# FAN.net
KiCad netlist of a schematic drawn in Altium Designer
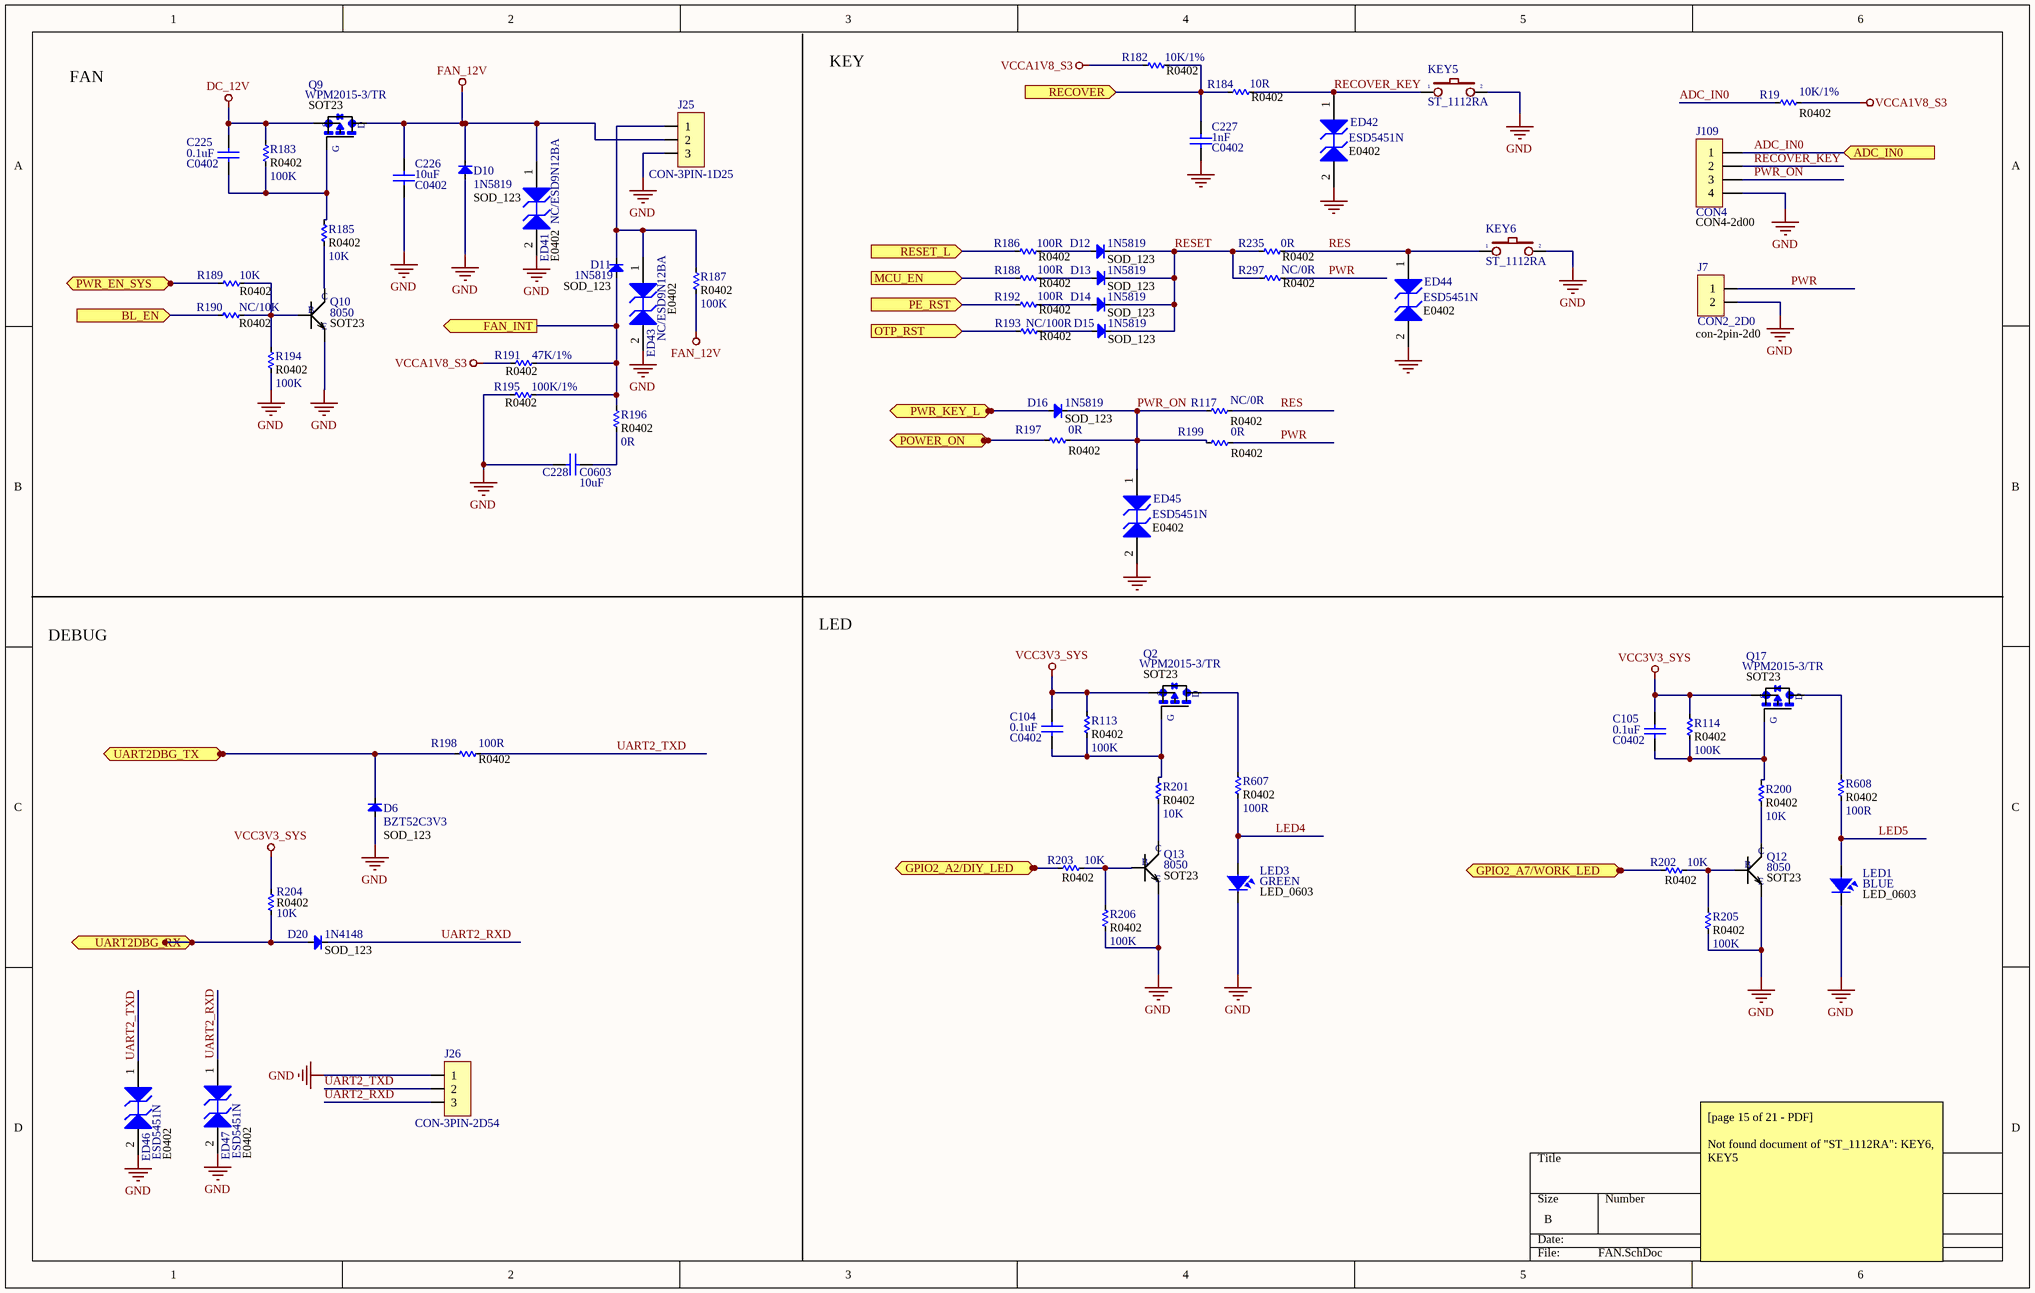
[diagram p0: FAN.SchDoc]

(export (version "E")
  (design (tool "Eeschema 10.0.6"))
  (components
    (comp (ref "C104")
      (value "C0402")
      (footprint "C 0402")
      (description "Capacitor")
      (fields (field (name "ALTIUM_VALUE") "0.1uF") (field (name "PUBLISHER") "Altium Limited"))
      (libsource (lib "Miscellaneous Devices") (part "Cap"))
    )
    (comp (ref "C105")
      (value "C0402")
      (footprint "C 0402")
      (description "Capacitor")
      (fields (field (name "ALTIUM_VALUE") "0.1uF") (field (name "PUBLISHER") "Altium Limited"))
      (libsource (lib "Miscellaneous Devices") (part "Cap"))
    )
    (comp (ref "C225")
      (value "C0402")
      (footprint "C 0402")
      (description "Capacitor")
      (fields (field (name "ALTIUM_VALUE") "0.1uF") (field (name "PUBLISHER") "Altium Limited"))
      (libsource (lib "Miscellaneous Devices") (part "Cap"))
    )
    (comp (ref "C226")
      (value "C0402")
      (footprint "C 0402")
      (description "Capacitor")
      (fields (field (name "ALTIUM_VALUE") "10uF") (field (name "PUBLISHER") "Altium Limited"))
      (libsource (lib "Miscellaneous Devices") (part "Cap"))
    )
    (comp (ref "C227")
      (value "C0402")
      (footprint "C 0402")
      (description "Capacitor")
      (fields (field (name "ALTIUM_VALUE") "1nF") (field (name "PUBLISHER") "Altium Limited"))
      (libsource (lib "Miscellaneous Devices") (part "Cap"))
    )
    (comp (ref "C228")
      (value "C0603")
      (footprint "C 0603")
      (description "Capacitor")
      (fields (field (name "ALTIUM_VALUE") "10uF") (field (name "PUBLISHER") "Altium Limited"))
      (libsource (lib "Miscellaneous Devices") (part "Cap"))
    )
    (comp (ref "D6")
      (value "BZT52C3V3")
      (footprint "DIO-SMD-123")
      (description "Default Diode")
      (fields (field (name "TYPR") "SOD_123") (field (name "PUBLISHER") "Altium Limited"))
      (libsource (lib "LIBRARY") (part "Diode SMD"))
    )
    (comp (ref "D10")
      (value "1N5819")
      (footprint "DIO-SMD-123")
      (description "Default Diode")
      (fields
        (field (name "TYPR") "SOD_123")
        (field (name "Comment") "Diode SMD")
        (field (name "PUBLISHER") "Altium Limited")
      )
      (libsource (lib "LIBRARY") (part "Diode SMD"))
    )
    (comp (ref "D11")
      (value "1N5819")
      (footprint "DIO-SMD-123")
      (description "Default Diode")
      (fields
        (field (name "TYPR") "SOD_123")
        (field (name "Comment") "Diode SMD")
        (field (name "PUBLISHER") "Altium Limited")
      )
      (libsource (lib "LIBRARY") (part "Diode SMD"))
    )
    (comp (ref "D12")
      (value "1N5819")
      (footprint "DIO-SMD-123")
      (description "Default Diode")
      (fields
        (field (name "TYPR") "SOD_123")
        (field (name "Comment") "Diode SMD")
        (field (name "PUBLISHER") "Altium Limited")
      )
      (libsource (lib "LIBRARY") (part "Diode SMD"))
    )
    (comp (ref "D13")
      (value "1N5819")
      (footprint "DIO-SMD-123")
      (description "Default Diode")
      (fields
        (field (name "TYPR") "SOD_123")
        (field (name "Comment") "Diode SMD")
        (field (name "PUBLISHER") "Altium Limited")
      )
      (libsource (lib "LIBRARY") (part "Diode SMD"))
    )
    (comp (ref "D14")
      (value "1N5819")
      (footprint "DIO-SMD-123")
      (description "Default Diode")
      (fields
        (field (name "TYPR") "SOD_123")
        (field (name "Comment") "Diode SMD")
        (field (name "PUBLISHER") "Altium Limited")
      )
      (libsource (lib "LIBRARY") (part "Diode SMD"))
    )
    (comp (ref "D15")
      (value "1N5819")
      (footprint "DIO-SMD-123")
      (description "Default Diode")
      (fields
        (field (name "TYPR") "SOD_123")
        (field (name "Comment") "Diode SMD")
        (field (name "PUBLISHER") "Altium Limited")
      )
      (libsource (lib "LIBRARY") (part "Diode SMD"))
    )
    (comp (ref "D16")
      (value "1N5819")
      (footprint "DIO-SMD-123")
      (description "Default Diode")
      (fields
        (field (name "TYPR") "SOD_123")
        (field (name "Comment") "Diode SMD")
        (field (name "PUBLISHER") "Altium Limited")
      )
      (libsource (lib "LIBRARY") (part "Diode SMD"))
    )
    (comp (ref "D20")
      (value "1N4148")
      (footprint "DIO-SMD-123")
      (description "Default Diode")
      (fields
        (field (name "TYPR") "SOD_123")
        (field (name "Comment") "Diode SMD")
        (field (name "PUBLISHER") "Altium Limited")
      )
      (libsource (lib "LIBRARY") (part "Diode SMD"))
    )
    (comp (ref "ED41")
      (value "NC/ESD9N12BA")
      (footprint "DFN1006-2L")
      (description "600 W Peak Power Zener Transient Voltage Suppressor, Bidirectional, 2-Pin SMB, Tape and Reel")
      (fields
        (field (name "MANUFACTURER") "On Semiconductor")
        (field (name "PARTNUMBER") "1SMB54CAT3")
        (field (name "ALTIUM_UNNAMED_1") "E0402")
      )
      (libsource (lib "ON Semi Transient Voltage Suppressors (TVS)") (part "1SMB54CAT3"))
    )
    (comp (ref "ED42")
      (value "ESD5451N")
      (footprint "DFN1006-2L")
      (description "600 W Peak Power Zener Transient Voltage Suppressor, Bidirectional, 2-Pin SMB, Tape and Reel")
      (fields
        (field (name "MANUFACTURER") "On Semiconductor")
        (field (name "PARTNUMBER") "1SMB54CAT3")
        (field (name "ALTIUM_UNNAMED_1") "E0402")
      )
      (libsource (lib "ON Semi Transient Voltage Suppressors (TVS)") (part "1SMB54CAT3"))
    )
    (comp (ref "ED43")
      (value "NC/ESD9N12BA")
      (footprint "DFN1006-2L")
      (description "600 W Peak Power Zener Transient Voltage Suppressor, Bidirectional, 2-Pin SMB, Tape and Reel")
      (fields
        (field (name "MANUFACTURER") "On Semiconductor")
        (field (name "PARTNUMBER") "1SMB54CAT3")
        (field (name "ALTIUM_UNNAMED_1") "E0402")
      )
      (libsource (lib "ON Semi Transient Voltage Suppressors (TVS)") (part "1SMB54CAT3"))
    )
    (comp (ref "ED44")
      (value "ESD5451N")
      (footprint "DFN1006-2L")
      (description "600 W Peak Power Zener Transient Voltage Suppressor, Bidirectional, 2-Pin SMB, Tape and Reel")
      (fields
        (field (name "MANUFACTURER") "On Semiconductor")
        (field (name "PARTNUMBER") "1SMB54CAT3")
        (field (name "ALTIUM_UNNAMED_1") "E0402")
      )
      (libsource (lib "ON Semi Transient Voltage Suppressors (TVS)") (part "1SMB54CAT3"))
    )
    (comp (ref "ED45")
      (value "ESD5451N")
      (footprint "DFN1006-2L")
      (description "600 W Peak Power Zener Transient Voltage Suppressor, Bidirectional, 2-Pin SMB, Tape and Reel")
      (fields
        (field (name "MANUFACTURER") "On Semiconductor")
        (field (name "PARTNUMBER") "1SMB54CAT3")
        (field (name "ALTIUM_UNNAMED_1") "E0402")
      )
      (libsource (lib "ON Semi Transient Voltage Suppressors (TVS)") (part "1SMB54CAT3"))
    )
    (comp (ref "ED46")
      (value "ESD5451N")
      (footprint "DFN1006-2L")
      (description "600 W Peak Power Zener Transient Voltage Suppressor, Bidirectional, 2-Pin SMB, Tape and Reel")
      (fields
        (field (name "MANUFACTURER") "On Semiconductor")
        (field (name "PARTNUMBER") "1SMB54CAT3")
        (field (name "ALTIUM_UNNAMED_1") "E0402")
      )
      (libsource (lib "ON Semi Transient Voltage Suppressors (TVS)") (part "1SMB54CAT3"))
    )
    (comp (ref "ED47")
      (value "ESD5451N")
      (footprint "DFN1006-2L")
      (description "600 W Peak Power Zener Transient Voltage Suppressor, Bidirectional, 2-Pin SMB, Tape and Reel")
      (fields
        (field (name "MANUFACTURER") "On Semiconductor")
        (field (name "PARTNUMBER") "1SMB54CAT3")
        (field (name "ALTIUM_UNNAMED_1") "E0402")
      )
      (libsource (lib "ON Semi Transient Voltage Suppressors (TVS)") (part "1SMB54CAT3"))
    )
    (comp (ref "J7")
      (value "CON2_2D0")
      (footprint "CON2")
      (description "WR-PHD 2.54 mm Angled Socket Header")
      (fields
        (field (name "MANUFACTURER") "Würth Elektronik eiSos GmbH")
        (field (name "PARTNO") "613002143121")
        (field (name "ALTIUM_UNNAMED_1") "con-2pin-2d0")
        (field (name "CREATED BY") "Karrer Zheng")
      )
      (libsource (lib "LIBRARY") (part "JP2"))
    )
    (comp (ref "J25")
      (value "CON-3PIN-1D25")
      (footprint "CON3")
      (description "WR-PHD 2.54 mm Angled Socket Header")
      (fields
        (field (name "MANUFACTURER") "Würth Elektronik eiSos GmbH")
        (field (name "PARTNO") "613003143121")
        (field (name "CREATED BY") "Karrer Zheng")
      )
      (libsource (lib "LIBRARY") (part "JP3"))
    )
    (comp (ref "J26")
      (value "CON-3PIN-2D54")
      (footprint "CON3")
      (description "WR-PHD 2.54 mm Angled Socket Header")
      (fields
        (field (name "MANUFACTURER") "Würth Elektronik eiSos GmbH")
        (field (name "PARTNO") "613003143121")
        (field (name "CREATED BY") "Karrer Zheng")
      )
      (libsource (lib "LIBRARY") (part "JP3"))
    )
    (comp (ref "J109")
      (value "CON4")
      (footprint "CON4")
      (description "WR-PHD 2.00 mm Socket Header")
      (fields
        (field (name "MANUFACTURER") "Würth Elektronik eiSos GmbH")
        (field (name "PARTNO") "62000411821")
        (field (name "ALTIUM_UNNAMED_1") "CON4-2d00")
        (field (name "CREATED BY") "Karrer Zheng")
      )
      (libsource (lib "LIBRARY") (part "JP4x1-2.0"))
    )
    (comp (ref "KEY5")
      (value "ST_1112RA")
      (footprint "SW1-SMD")
      (description "Switch button 2 pin")
      (libsource (lib "LIBRARY") (part "SW2"))
    )
    (comp (ref "KEY6")
      (value "ST_1112RA")
      (footprint "SW1-SMD")
      (description "Switch button 2 pin")
      (libsource (lib "LIBRARY") (part "SW2"))
    )
    (comp (ref "LED1")
      (value "LED SMD")
      (footprint "SM-LED-0805-Blue")
      (fields (field (name "PACKAGE") "LED_0603") (field (name "COLOR") "BLUE"))
      (libsource (lib "syhaunguyen") (part "LED-SMD-0805"))
    )
    (comp (ref "LED3")
      (value "LED SMD")
      (footprint "SM-LED-0805-Green")
      (fields (field (name "PACKAGE") "LED_0603") (field (name "COLOR") "GREEN"))
      (libsource (lib "syhaunguyen") (part "LED-SMD-0805"))
    )
    (comp (ref "Q2")
      (value "WPM2015-3/TR")
      (footprint "*SSOT-3")
      (description "P-Channel 20 V 52 mOhm 1.8V Surface Mount Specified PowerTrench Mosfet SSOT-3")
      (fields
        (field (name "MF") "ON Semiconductor")
        (field (name "MP") "FDN304P")
        (field (name "ALTIUM_UNNAMED_1") "SOT23")
      )
      (libsource (lib "FDN304P") (part "FDN304P"))
    )
    (comp (ref "Q9")
      (value "WPM2015-3/TR")
      (footprint "*SSOT-3")
      (description "P-Channel 20 V 52 mOhm 1.8V Surface Mount Specified PowerTrench Mosfet SSOT-3")
      (fields
        (field (name "MF") "ON Semiconductor")
        (field (name "MP") "FDN304P")
        (field (name "ALTIUM_UNNAMED_1") "SOT23")
      )
      (libsource (lib "") (part "FDN304P_2"))
    )
    (comp (ref "Q10")
      (value "8050")
      (footprint "*SOT-23")
      (fields
        (field (name "MF") "Recom Power")
        (field (name "MP") "S8050")
        (field (name "ALTIUM_UNNAMED_1") "SOT23")
      )
      (libsource (lib "SMD-TRANSISTORS-NPN-25V-500MW_SOT-23_") (part "SMD-TRANSISTORS-NPN-25V-500MW(SOT-23)"))
    )
    (comp (ref "Q12")
      (value "8050")
      (footprint "*SOT-23")
      (fields
        (field (name "MF") "Recom Power")
        (field (name "MP") "S8050")
        (field (name "ALTIUM_UNNAMED_1") "SOT23")
      )
      (libsource (lib "SMD-TRANSISTORS-NPN-25V-500MW_SOT-23_") (part "SMD-TRANSISTORS-NPN-25V-500MW(SOT-23)"))
    )
    (comp (ref "Q13")
      (value "8050")
      (footprint "*SOT-23")
      (fields
        (field (name "MF") "Recom Power")
        (field (name "MP") "S8050")
        (field (name "ALTIUM_UNNAMED_1") "SOT23")
      )
      (libsource (lib "SMD-TRANSISTORS-NPN-25V-500MW_SOT-23_") (part "SMD-TRANSISTORS-NPN-25V-500MW(SOT-23)"))
    )
    (comp (ref "Q17")
      (value "WPM2015-3/TR")
      (footprint "*SSOT-3")
      (description "P-Channel 20 V 52 mOhm 1.8V Surface Mount Specified PowerTrench Mosfet SSOT-3")
      (fields
        (field (name "MF") "ON Semiconductor")
        (field (name "MP") "FDN304P")
        (field (name "ALTIUM_UNNAMED_1") "SOT23")
      )
      (libsource (lib "") (part "FDN304P_1"))
    )
    (comp (ref "R19")
      (value "R0402")
      (footprint "R 0402")
      (description "Resistor")
      (fields
        (field (name "MANUFACTURER") "Generic Components")
        (field (name "ALTIUM_VALUE") "10K/1%")
        (field (name "PUBLISHER") "Altium Hobart Technology Centre")
      )
      (libsource (lib "LIBRARY") (part "Res-SMD"))
    )
    (comp (ref "R113")
      (value "R0402")
      (footprint "R 0402")
      (description "Resistor")
      (fields
        (field (name "MANUFACTURER") "Generic Components")
        (field (name "ALTIUM_VALUE") "100K")
        (field (name "PUBLISHER") "Altium Hobart Technology Centre")
      )
      (libsource (lib "LIBRARY") (part "Res-SMD"))
    )
    (comp (ref "R114")
      (value "R0402")
      (footprint "R 0402")
      (description "Resistor")
      (fields
        (field (name "MANUFACTURER") "Generic Components")
        (field (name "ALTIUM_VALUE") "100K")
        (field (name "PUBLISHER") "Altium Hobart Technology Centre")
      )
      (libsource (lib "LIBRARY") (part "Res-SMD"))
    )
    (comp (ref "R117")
      (value "R0402")
      (footprint "R 0402")
      (description "Resistor")
      (fields
        (field (name "MANUFACTURER") "Generic Components")
        (field (name "ALTIUM_VALUE") "NC/0R")
        (field (name "PUBLISHER") "Altium Hobart Technology Centre")
      )
      (libsource (lib "LIBRARY") (part "Res-SMD"))
    )
    (comp (ref "R182")
      (value "R0402")
      (footprint "R 0402")
      (description "Resistor")
      (fields
        (field (name "MANUFACTURER") "Generic Components")
        (field (name "ALTIUM_VALUE") "10K/1%")
        (field (name "PUBLISHER") "Altium Hobart Technology Centre")
      )
      (libsource (lib "LIBRARY") (part "Res-SMD"))
    )
    (comp (ref "R183")
      (value "R0402")
      (footprint "R 0402")
      (description "Resistor")
      (fields
        (field (name "MANUFACTURER") "Generic Components")
        (field (name "ALTIUM_VALUE") "100K")
        (field (name "PUBLISHER") "Altium Hobart Technology Centre")
      )
      (libsource (lib "LIBRARY") (part "Res-SMD"))
    )
    (comp (ref "R184")
      (value "R0402")
      (footprint "R 0402")
      (description "Resistor")
      (fields
        (field (name "MANUFACTURER") "Generic Components")
        (field (name "ALTIUM_VALUE") "10R")
        (field (name "PUBLISHER") "Altium Hobart Technology Centre")
      )
      (libsource (lib "LIBRARY") (part "Res-SMD"))
    )
    (comp (ref "R185")
      (value "R0402")
      (footprint "R 0402")
      (description "Resistor")
      (fields
        (field (name "MANUFACTURER") "Generic Components")
        (field (name "ALTIUM_VALUE") "10K")
        (field (name "PUBLISHER") "Altium Hobart Technology Centre")
      )
      (libsource (lib "LIBRARY") (part "Res-SMD"))
    )
    (comp (ref "R186")
      (value "R0402")
      (footprint "R 0402")
      (description "Resistor")
      (fields
        (field (name "MANUFACTURER") "Generic Components")
        (field (name "ALTIUM_VALUE") "100R")
        (field (name "PUBLISHER") "Altium Hobart Technology Centre")
      )
      (libsource (lib "LIBRARY") (part "Res-SMD"))
    )
    (comp (ref "R187")
      (value "R0402")
      (footprint "R 0402")
      (description "Resistor")
      (fields
        (field (name "MANUFACTURER") "Generic Components")
        (field (name "ALTIUM_VALUE") "100K")
        (field (name "PUBLISHER") "Altium Hobart Technology Centre")
      )
      (libsource (lib "LIBRARY") (part "Res-SMD"))
    )
    (comp (ref "R188")
      (value "R0402")
      (footprint "R 0402")
      (description "Resistor")
      (fields
        (field (name "MANUFACTURER") "Generic Components")
        (field (name "ALTIUM_VALUE") "100R")
        (field (name "PUBLISHER") "Altium Hobart Technology Centre")
      )
      (libsource (lib "LIBRARY") (part "Res-SMD"))
    )
    (comp (ref "R189")
      (value "R0402")
      (footprint "R 0402")
      (description "Resistor")
      (fields
        (field (name "MANUFACTURER") "Generic Components")
        (field (name "ALTIUM_VALUE") "10K")
        (field (name "PUBLISHER") "Altium Hobart Technology Centre")
      )
      (libsource (lib "LIBRARY") (part "Res-SMD"))
    )
    (comp (ref "R190")
      (value "R0402")
      (footprint "R 0402")
      (description "Resistor")
      (fields
        (field (name "MANUFACTURER") "Generic Components")
        (field (name "ALTIUM_VALUE") "NC/10K")
        (field (name "PUBLISHER") "Altium Hobart Technology Centre")
      )
      (libsource (lib "LIBRARY") (part "Res-SMD"))
    )
    (comp (ref "R191")
      (value "R0402")
      (footprint "R 0402")
      (description "Resistor")
      (fields
        (field (name "MANUFACTURER") "Generic Components")
        (field (name "ALTIUM_VALUE") "47K/1%")
        (field (name "PUBLISHER") "Altium Hobart Technology Centre")
      )
      (libsource (lib "LIBRARY") (part "Res-SMD"))
    )
    (comp (ref "R192")
      (value "R0402")
      (footprint "R 0402")
      (description "Resistor")
      (fields
        (field (name "MANUFACTURER") "Generic Components")
        (field (name "ALTIUM_VALUE") "100R")
        (field (name "PUBLISHER") "Altium Hobart Technology Centre")
      )
      (libsource (lib "LIBRARY") (part "Res-SMD"))
    )
    (comp (ref "R193")
      (value "R0402")
      (footprint "R 0402")
      (description "Resistor")
      (fields
        (field (name "MANUFACTURER") "Generic Components")
        (field (name "ALTIUM_VALUE") "NC/100R")
        (field (name "PUBLISHER") "Altium Hobart Technology Centre")
      )
      (libsource (lib "LIBRARY") (part "Res-SMD"))
    )
    (comp (ref "R194")
      (value "R0402")
      (footprint "R 0402")
      (description "Resistor")
      (fields
        (field (name "MANUFACTURER") "Generic Components")
        (field (name "ALTIUM_VALUE") "100K")
        (field (name "PUBLISHER") "Altium Hobart Technology Centre")
      )
      (libsource (lib "LIBRARY") (part "Res-SMD"))
    )
    (comp (ref "R195")
      (value "R0402")
      (footprint "R 0402")
      (description "Resistor")
      (fields
        (field (name "MANUFACTURER") "Generic Components")
        (field (name "ALTIUM_VALUE") "100K/1%")
        (field (name "PUBLISHER") "Altium Hobart Technology Centre")
      )
      (libsource (lib "LIBRARY") (part "Res-SMD"))
    )
    (comp (ref "R196")
      (value "R0402")
      (footprint "R 0402")
      (description "Resistor")
      (fields
        (field (name "MANUFACTURER") "Generic Components")
        (field (name "ALTIUM_VALUE") "0R")
        (field (name "PUBLISHER") "Altium Hobart Technology Centre")
      )
      (libsource (lib "LIBRARY") (part "Res-SMD"))
    )
    (comp (ref "R197")
      (value "R0402")
      (footprint "R 0402")
      (description "Resistor")
      (fields
        (field (name "MANUFACTURER") "Generic Components")
        (field (name "ALTIUM_VALUE") "0R")
        (field (name "PUBLISHER") "Altium Hobart Technology Centre")
      )
      (libsource (lib "LIBRARY") (part "Res-SMD"))
    )
    (comp (ref "R198")
      (value "R0402")
      (footprint "R 0402")
      (description "Resistor")
      (fields
        (field (name "MANUFACTURER") "Generic Components")
        (field (name "ALTIUM_VALUE") "100R")
        (field (name "PUBLISHER") "Altium Hobart Technology Centre")
      )
      (libsource (lib "LIBRARY") (part "Res-SMD"))
    )
    (comp (ref "R199")
      (value "R0402")
      (footprint "R 0402")
      (description "Resistor")
      (fields
        (field (name "MANUFACTURER") "Generic Components")
        (field (name "ALTIUM_VALUE") "0R")
        (field (name "PUBLISHER") "Altium Hobart Technology Centre")
      )
      (libsource (lib "LIBRARY") (part "Res-SMD"))
    )
    (comp (ref "R200")
      (value "R0402")
      (footprint "R 0402")
      (description "Resistor")
      (fields
        (field (name "MANUFACTURER") "Generic Components")
        (field (name "ALTIUM_VALUE") "10K")
        (field (name "PUBLISHER") "Altium Hobart Technology Centre")
      )
      (libsource (lib "LIBRARY") (part "Res-SMD"))
    )
    (comp (ref "R201")
      (value "R0402")
      (footprint "R 0402")
      (description "Resistor")
      (fields
        (field (name "MANUFACTURER") "Generic Components")
        (field (name "ALTIUM_VALUE") "10K")
        (field (name "PUBLISHER") "Altium Hobart Technology Centre")
      )
      (libsource (lib "LIBRARY") (part "Res-SMD"))
    )
    (comp (ref "R202")
      (value "R0402")
      (footprint "R 0402")
      (description "Resistor")
      (fields
        (field (name "MANUFACTURER") "Generic Components")
        (field (name "ALTIUM_VALUE") "10K")
        (field (name "PUBLISHER") "Altium Hobart Technology Centre")
      )
      (libsource (lib "LIBRARY") (part "Res-SMD"))
    )
    (comp (ref "R203")
      (value "R0402")
      (footprint "R 0402")
      (description "Resistor")
      (fields
        (field (name "MANUFACTURER") "Generic Components")
        (field (name "ALTIUM_VALUE") "10K")
        (field (name "PUBLISHER") "Altium Hobart Technology Centre")
      )
      (libsource (lib "LIBRARY") (part "Res-SMD"))
    )
    (comp (ref "R204")
      (value "R0402")
      (footprint "R 0402")
      (description "Resistor")
      (fields
        (field (name "MANUFACTURER") "Generic Components")
        (field (name "ALTIUM_VALUE") "10K")
        (field (name "PUBLISHER") "Altium Hobart Technology Centre")
      )
      (libsource (lib "LIBRARY") (part "Res-SMD"))
    )
    (comp (ref "R205")
      (value "R0402")
      (footprint "R 0402")
      (description "Resistor")
      (fields
        (field (name "MANUFACTURER") "Generic Components")
        (field (name "ALTIUM_VALUE") "100K")
        (field (name "PUBLISHER") "Altium Hobart Technology Centre")
      )
      (libsource (lib "LIBRARY") (part "Res-SMD"))
    )
    (comp (ref "R206")
      (value "R0402")
      (footprint "R 0402")
      (description "Resistor")
      (fields
        (field (name "MANUFACTURER") "Generic Components")
        (field (name "ALTIUM_VALUE") "100K")
        (field (name "PUBLISHER") "Altium Hobart Technology Centre")
      )
      (libsource (lib "LIBRARY") (part "Res-SMD"))
    )
    (comp (ref "R235")
      (value "R0402")
      (footprint "R 0402")
      (description "Resistor")
      (fields
        (field (name "MANUFACTURER") "Generic Components")
        (field (name "ALTIUM_VALUE") "0R")
        (field (name "PUBLISHER") "Altium Hobart Technology Centre")
      )
      (libsource (lib "LIBRARY") (part "Res-SMD"))
    )
    (comp (ref "R297")
      (value "R0402")
      (footprint "R 0402")
      (description "Resistor")
      (fields
        (field (name "MANUFACTURER") "Generic Components")
        (field (name "ALTIUM_VALUE") "NC/0R")
        (field (name "PUBLISHER") "Altium Hobart Technology Centre")
      )
      (libsource (lib "LIBRARY") (part "Res-SMD"))
    )
    (comp (ref "R607")
      (value "R0402")
      (footprint "R 0402")
      (description "Resistor")
      (fields
        (field (name "MANUFACTURER") "Generic Components")
        (field (name "ALTIUM_VALUE") "100R")
        (field (name "PUBLISHER") "Altium Hobart Technology Centre")
      )
      (libsource (lib "LIBRARY") (part "Res-SMD"))
    )
    (comp (ref "R608")
      (value "R0402")
      (footprint "R 0402")
      (description "Resistor")
      (fields
        (field (name "MANUFACTURER") "Generic Components")
        (field (name "ALTIUM_VALUE") "100R")
        (field (name "PUBLISHER") "Altium Hobart Technology Centre")
      )
      (libsource (lib "LIBRARY") (part "Res-SMD"))
    )
  )
  (nets
    (net (code "1") (name "/ADC_IN0") (class "Default")
      (node (ref "J109") (pin "1") (pinfunction "1_1") (pintype "passive"))
      (node (ref "R19") (pin "1") (pinfunction "1_1") (pintype "passive"))
    )
    (net (code "2") (name "/BL_EN") (class "Default")
      (node (ref "R190") (pin "2") (pinfunction "2_2") (pintype "passive"))
    )
    (net (code "3") (name "/FAN_INT") (class "Default")
      (node (ref "D11") (pin "1") (pinfunction "A_1") (pintype "passive"))
      (node (ref "R191") (pin "1") (pinfunction "1_1") (pintype "passive"))
      (node (ref "R195") (pin "1") (pinfunction "1_1") (pintype "passive"))
      (node (ref "R196") (pin "1") (pinfunction "1_1") (pintype "passive"))
    )
    (net (code "4") (name "/GPIO2_A2{slash}DIY_LED") (class "Default")
      (node (ref "R203") (pin "1") (pinfunction "1_1") (pintype "passive"))
    )
    (net (code "5") (name "/GPIO2_A7{slash}WORK_LED") (class "Default")
      (node (ref "R202") (pin "1") (pinfunction "1_1") (pintype "passive"))
    )
    (net (code "6") (name "/LED4") (class "Default")
      (node (ref "LED3") (pin "1") (pinfunction "1_1") (pintype "passive"))
      (node (ref "R607") (pin "2") (pinfunction "2_2") (pintype "passive"))
    )
    (net (code "7") (name "/LED5") (class "Default")
      (node (ref "LED1") (pin "1") (pinfunction "1_1") (pintype "passive"))
      (node (ref "R608") (pin "2") (pinfunction "2_2") (pintype "passive"))
    )
    (net (code "8") (name "/MCU_EN") (class "Default")
      (node (ref "R188") (pin "1") (pinfunction "1_1") (pintype "passive"))
    )
    (net (code "9") (name "/OTP_RST") (class "Default")
      (node (ref "R193") (pin "1") (pinfunction "1_1") (pintype "passive"))
    )
    (net (code "10") (name "/PE_RST") (class "Default")
      (node (ref "R192") (pin "1") (pinfunction "1_1") (pintype "passive"))
    )
    (net (code "11") (name "/POWER_ON") (class "Default")
      (node (ref "R197") (pin "1") (pinfunction "1_1") (pintype "passive"))
    )
    (net (code "12") (name "/PWR") (class "Default")
      (node (ref "J7") (pin "1") (pinfunction "1_1") (pintype "passive"))
      (node (ref "R199") (pin "2") (pinfunction "2_2") (pintype "passive"))
      (node (ref "R297") (pin "2") (pinfunction "2_2") (pintype "passive"))
    )
    (net (code "13") (name "/PWR_EN_SYS") (class "Default")
      (node (ref "R189") (pin "2") (pinfunction "2_2") (pintype "passive"))
    )
    (net (code "14") (name "/PWR_KEY_L") (class "Default")
      (node (ref "D16") (pin "1") (pinfunction "A_1") (pintype "passive"))
    )
    (net (code "15") (name "/PWR_ON") (class "Default")
      (node (ref "D16") (pin "2") (pinfunction "K_2") (pintype "passive"))
      (node (ref "ED45") (pin "1") (pinfunction "A1_1") (pintype "passive"))
      (node (ref "J109") (pin "3") (pinfunction "3_3") (pintype "passive"))
      (node (ref "R117") (pin "1") (pinfunction "1_1") (pintype "passive"))
      (node (ref "R197") (pin "2") (pinfunction "2_2") (pintype "passive"))
      (node (ref "R199") (pin "1") (pinfunction "1_1") (pintype "passive"))
    )
    (net (code "16") (name "/RECOVER") (class "Default")
      (node (ref "C227") (pin "1") (pinfunction "1_1") (pintype "passive"))
      (node (ref "R182") (pin "2") (pinfunction "2_2") (pintype "passive"))
      (node (ref "R184") (pin "1") (pinfunction "1_1") (pintype "passive"))
    )
    (net (code "17") (name "/RECOVER_KEY") (class "Default")
      (node (ref "ED42") (pin "1") (pinfunction "A1_1") (pintype "passive"))
      (node (ref "J109") (pin "2") (pinfunction "2_2") (pintype "passive"))
      (node (ref "KEY5") (pin "1") (pinfunction "1_1") (pintype "passive"))
      (node (ref "R184") (pin "2") (pinfunction "2_2") (pintype "passive"))
    )
    (net (code "18") (name "/RES") (class "Default")
      (node (ref "ED44") (pin "1") (pinfunction "A1_1") (pintype "passive"))
      (node (ref "KEY6") (pin "1") (pinfunction "1_1") (pintype "passive"))
      (node (ref "R117") (pin "2") (pinfunction "2_2") (pintype "passive"))
      (node (ref "R235") (pin "2") (pinfunction "2_2") (pintype "passive"))
    )
    (net (code "19") (name "/RESET") (class "Default")
      (node (ref "D12") (pin "2") (pinfunction "K_2") (pintype "passive"))
      (node (ref "D13") (pin "2") (pinfunction "K_2") (pintype "passive"))
      (node (ref "D14") (pin "2") (pinfunction "K_2") (pintype "passive"))
      (node (ref "D15") (pin "2") (pinfunction "K_2") (pintype "passive"))
      (node (ref "R235") (pin "1") (pinfunction "1_1") (pintype "passive"))
      (node (ref "R297") (pin "1") (pinfunction "1_1") (pintype "passive"))
    )
    (net (code "20") (name "/RESET_L") (class "Default")
      (node (ref "R186") (pin "1") (pinfunction "1_1") (pintype "passive"))
    )
    (net (code "21") (name "/UART2DBG_RX") (class "Default")
      (node (ref "D20") (pin "1") (pinfunction "A_1") (pintype "passive"))
      (node (ref "R204") (pin "2") (pinfunction "2_2") (pintype "passive"))
    )
    (net (code "22") (name "/UART2DBG_TX") (class "Default")
      (node (ref "D6") (pin "2") (pinfunction "K_2") (pintype "passive"))
      (node (ref "R198") (pin "1") (pinfunction "1_1") (pintype "passive"))
    )
    (net (code "23") (name "/UART2_RXD") (class "Default")
      (node (ref "D20") (pin "2") (pinfunction "K_2") (pintype "passive"))
      (node (ref "ED47") (pin "1") (pinfunction "A1_1") (pintype "passive"))
      (node (ref "J26") (pin "3") (pinfunction "3_3") (pintype "passive"))
    )
    (net (code "24") (name "/UART2_TXD") (class "Default")
      (node (ref "ED46") (pin "1") (pinfunction "A1_1") (pintype "passive"))
      (node (ref "J26") (pin "2") (pinfunction "2_2") (pintype "passive"))
      (node (ref "R198") (pin "2") (pinfunction "2_2") (pintype "passive"))
    )
    (net (code "25") (name "DC_12V") (class "Default")
      (node (ref "C225") (pin "1") (pinfunction "1_1") (pintype "passive"))
      (node (ref "Q9") (pin "2") (pinfunction "S_2") (pintype "passive"))
      (node (ref "R183") (pin "2") (pinfunction "2_2") (pintype "passive"))
    )
    (net (code "26") (name "FAN_12V") (class "Default")
      (node (ref "C226") (pin "1") (pinfunction "1_1") (pintype "passive"))
      (node (ref "D10") (pin "2") (pinfunction "K_2") (pintype "passive"))
      (node (ref "ED41") (pin "1") (pinfunction "A1_1") (pintype "passive"))
      (node (ref "J25") (pin "2") (pinfunction "2_2") (pintype "passive"))
      (node (ref "Q9") (pin "3") (pinfunction "D_3") (pintype "passive"))
      (node (ref "R187") (pin "1") (pinfunction "1_1") (pintype "passive"))
    )
    (net (code "27") (name "GND") (class "Default")
      (node (ref "C226") (pin "2") (pinfunction "2_2") (pintype "passive"))
      (node (ref "C227") (pin "2") (pinfunction "2_2") (pintype "passive"))
      (node (ref "C228") (pin "1") (pinfunction "1_1") (pintype "passive"))
      (node (ref "D10") (pin "1") (pinfunction "A_1") (pintype "passive"))
      (node (ref "D6") (pin "1") (pinfunction "A_1") (pintype "passive"))
      (node (ref "ED41") (pin "2") (pinfunction "A2_2") (pintype "passive"))
      (node (ref "ED42") (pin "2") (pinfunction "A2_2") (pintype "passive"))
      (node (ref "ED43") (pin "2") (pinfunction "A2_2") (pintype "passive"))
      (node (ref "ED44") (pin "2") (pinfunction "A2_2") (pintype "passive"))
      (node (ref "ED45") (pin "2") (pinfunction "A2_2") (pintype "passive"))
      (node (ref "ED46") (pin "2") (pinfunction "A2_2") (pintype "passive"))
      (node (ref "ED47") (pin "2") (pinfunction "A2_2") (pintype "passive"))
      (node (ref "J109") (pin "4") (pinfunction "4_4") (pintype "passive"))
      (node (ref "J25") (pin "3") (pinfunction "3_3") (pintype "passive"))
      (node (ref "J26") (pin "1") (pinfunction "1_1") (pintype "passive"))
      (node (ref "J7") (pin "2") (pinfunction "2_2") (pintype "passive"))
      (node (ref "KEY5") (pin "2") (pinfunction "2_2") (pintype "passive"))
      (node (ref "KEY6") (pin "2") (pinfunction "2_2") (pintype "passive"))
      (node (ref "LED1") (pin "2") (pinfunction "2_2") (pintype "passive"))
      (node (ref "LED3") (pin "2") (pinfunction "2_2") (pintype "passive"))
      (node (ref "Q10") (pin "2") (pinfunction "E_2") (pintype "passive"))
      (node (ref "Q12") (pin "2") (pinfunction "E_2") (pintype "passive"))
      (node (ref "Q13") (pin "2") (pinfunction "E_2") (pintype "passive"))
      (node (ref "R194") (pin "2") (pinfunction "2_2") (pintype "passive"))
      (node (ref "R195") (pin "2") (pinfunction "2_2") (pintype "passive"))
      (node (ref "R205") (pin "2") (pinfunction "2_2") (pintype "passive"))
      (node (ref "R206") (pin "2") (pinfunction "2_2") (pintype "passive"))
    )
    (net (code "28") (name "Net-(C228-Pad2)") (class "Default")
      (node (ref "C228") (pin "2") (pinfunction "2_2") (pintype "passive"))
      (node (ref "R196") (pin "2") (pinfunction "2_2") (pintype "passive"))
    )
    (net (code "29") (name "Net-(D11-K)") (class "Default")
      (node (ref "D11") (pin "2") (pinfunction "K_2") (pintype "passive"))
      (node (ref "ED43") (pin "1") (pinfunction "A1_1") (pintype "passive"))
      (node (ref "J25") (pin "1") (pinfunction "1_1") (pintype "passive"))
      (node (ref "R187") (pin "2") (pinfunction "2_2") (pintype "passive"))
    )
    (net (code "30") (name "Net-(D12-A)") (class "Default")
      (node (ref "D12") (pin "1") (pinfunction "A_1") (pintype "passive"))
      (node (ref "R186") (pin "2") (pinfunction "2_2") (pintype "passive"))
    )
    (net (code "31") (name "Net-(D13-A)") (class "Default")
      (node (ref "D13") (pin "1") (pinfunction "A_1") (pintype "passive"))
      (node (ref "R188") (pin "2") (pinfunction "2_2") (pintype "passive"))
    )
    (net (code "32") (name "Net-(D14-A)") (class "Default")
      (node (ref "D14") (pin "1") (pinfunction "A_1") (pintype "passive"))
      (node (ref "R192") (pin "2") (pinfunction "2_2") (pintype "passive"))
    )
    (net (code "33") (name "Net-(D15-A)") (class "Default")
      (node (ref "D15") (pin "1") (pinfunction "A_1") (pintype "passive"))
      (node (ref "R193") (pin "2") (pinfunction "2_2") (pintype "passive"))
    )
    (net (code "34") (name "Net-(Q2-D)") (class "Default")
      (node (ref "Q2") (pin "3") (pinfunction "D_3") (pintype "passive"))
      (node (ref "R607") (pin "1") (pinfunction "1_1") (pintype "passive"))
    )
    (net (code "35") (name "Net-(Q2-G)") (class "Default")
      (node (ref "C104") (pin "2") (pinfunction "2_2") (pintype "passive"))
      (node (ref "Q2") (pin "1") (pinfunction "G_1") (pintype "passive"))
      (node (ref "R113") (pin "2") (pinfunction "2_2") (pintype "passive"))
      (node (ref "R201") (pin "1") (pinfunction "1_1") (pintype "passive"))
    )
    (net (code "36") (name "Net-(Q9-G)") (class "Default")
      (node (ref "C225") (pin "2") (pinfunction "2_2") (pintype "passive"))
      (node (ref "Q9") (pin "1") (pinfunction "G_1") (pintype "passive"))
      (node (ref "R183") (pin "1") (pinfunction "1_1") (pintype "passive"))
      (node (ref "R185") (pin "2") (pinfunction "2_2") (pintype "passive"))
    )
    (net (code "37") (name "Net-(Q10-B)") (class "Default")
      (node (ref "Q10") (pin "1") (pinfunction "B_1") (pintype "passive"))
      (node (ref "R189") (pin "1") (pinfunction "1_1") (pintype "passive"))
      (node (ref "R190") (pin "1") (pinfunction "1_1") (pintype "passive"))
      (node (ref "R194") (pin "1") (pinfunction "1_1") (pintype "passive"))
    )
    (net (code "38") (name "Net-(Q10-C)") (class "Default")
      (node (ref "Q10") (pin "3") (pinfunction "C_3") (pintype "passive"))
      (node (ref "R185") (pin "1") (pinfunction "1_1") (pintype "passive"))
    )
    (net (code "39") (name "Net-(Q12-B)") (class "Default")
      (node (ref "Q12") (pin "1") (pinfunction "B_1") (pintype "passive"))
      (node (ref "R202") (pin "2") (pinfunction "2_2") (pintype "passive"))
      (node (ref "R205") (pin "1") (pinfunction "1_1") (pintype "passive"))
    )
    (net (code "40") (name "Net-(Q12-C)") (class "Default")
      (node (ref "Q12") (pin "3") (pinfunction "C_3") (pintype "passive"))
      (node (ref "R200") (pin "2") (pinfunction "2_2") (pintype "passive"))
    )
    (net (code "41") (name "Net-(Q13-B)") (class "Default")
      (node (ref "Q13") (pin "1") (pinfunction "B_1") (pintype "passive"))
      (node (ref "R203") (pin "2") (pinfunction "2_2") (pintype "passive"))
      (node (ref "R206") (pin "1") (pinfunction "1_1") (pintype "passive"))
    )
    (net (code "42") (name "Net-(Q13-C)") (class "Default")
      (node (ref "Q13") (pin "3") (pinfunction "C_3") (pintype "passive"))
      (node (ref "R201") (pin "2") (pinfunction "2_2") (pintype "passive"))
    )
    (net (code "43") (name "Net-(Q17-D)") (class "Default")
      (node (ref "Q17") (pin "3") (pinfunction "D_3") (pintype "passive"))
      (node (ref "R608") (pin "1") (pinfunction "1_1") (pintype "passive"))
    )
    (net (code "44") (name "Net-(Q17-G)") (class "Default")
      (node (ref "C105") (pin "2") (pinfunction "2_2") (pintype "passive"))
      (node (ref "Q17") (pin "1") (pinfunction "G_1") (pintype "passive"))
      (node (ref "R114") (pin "2") (pinfunction "2_2") (pintype "passive"))
      (node (ref "R200") (pin "1") (pinfunction "1_1") (pintype "passive"))
    )
    (net (code "45") (name "VCC3V3_SYS") (class "Default")
      (node (ref "C104") (pin "1") (pinfunction "1_1") (pintype "passive"))
      (node (ref "C105") (pin "1") (pinfunction "1_1") (pintype "passive"))
      (node (ref "Q17") (pin "2") (pinfunction "S_2") (pintype "passive"))
      (node (ref "Q2") (pin "2") (pinfunction "S_2") (pintype "passive"))
      (node (ref "R113") (pin "1") (pinfunction "1_1") (pintype "passive"))
      (node (ref "R114") (pin "1") (pinfunction "1_1") (pintype "passive"))
      (node (ref "R204") (pin "1") (pinfunction "1_1") (pintype "passive"))
    )
    (net (code "46") (name "VCCA1V8_S3") (class "Default")
      (node (ref "R182") (pin "1") (pinfunction "1_1") (pintype "passive"))
      (node (ref "R19") (pin "2") (pinfunction "2_2") (pintype "passive"))
      (node (ref "R191") (pin "2") (pinfunction "2_2") (pintype "passive"))
    )
  )
)
